# main_board.net
KiCad netlist of a schematic drawn in EAGLE
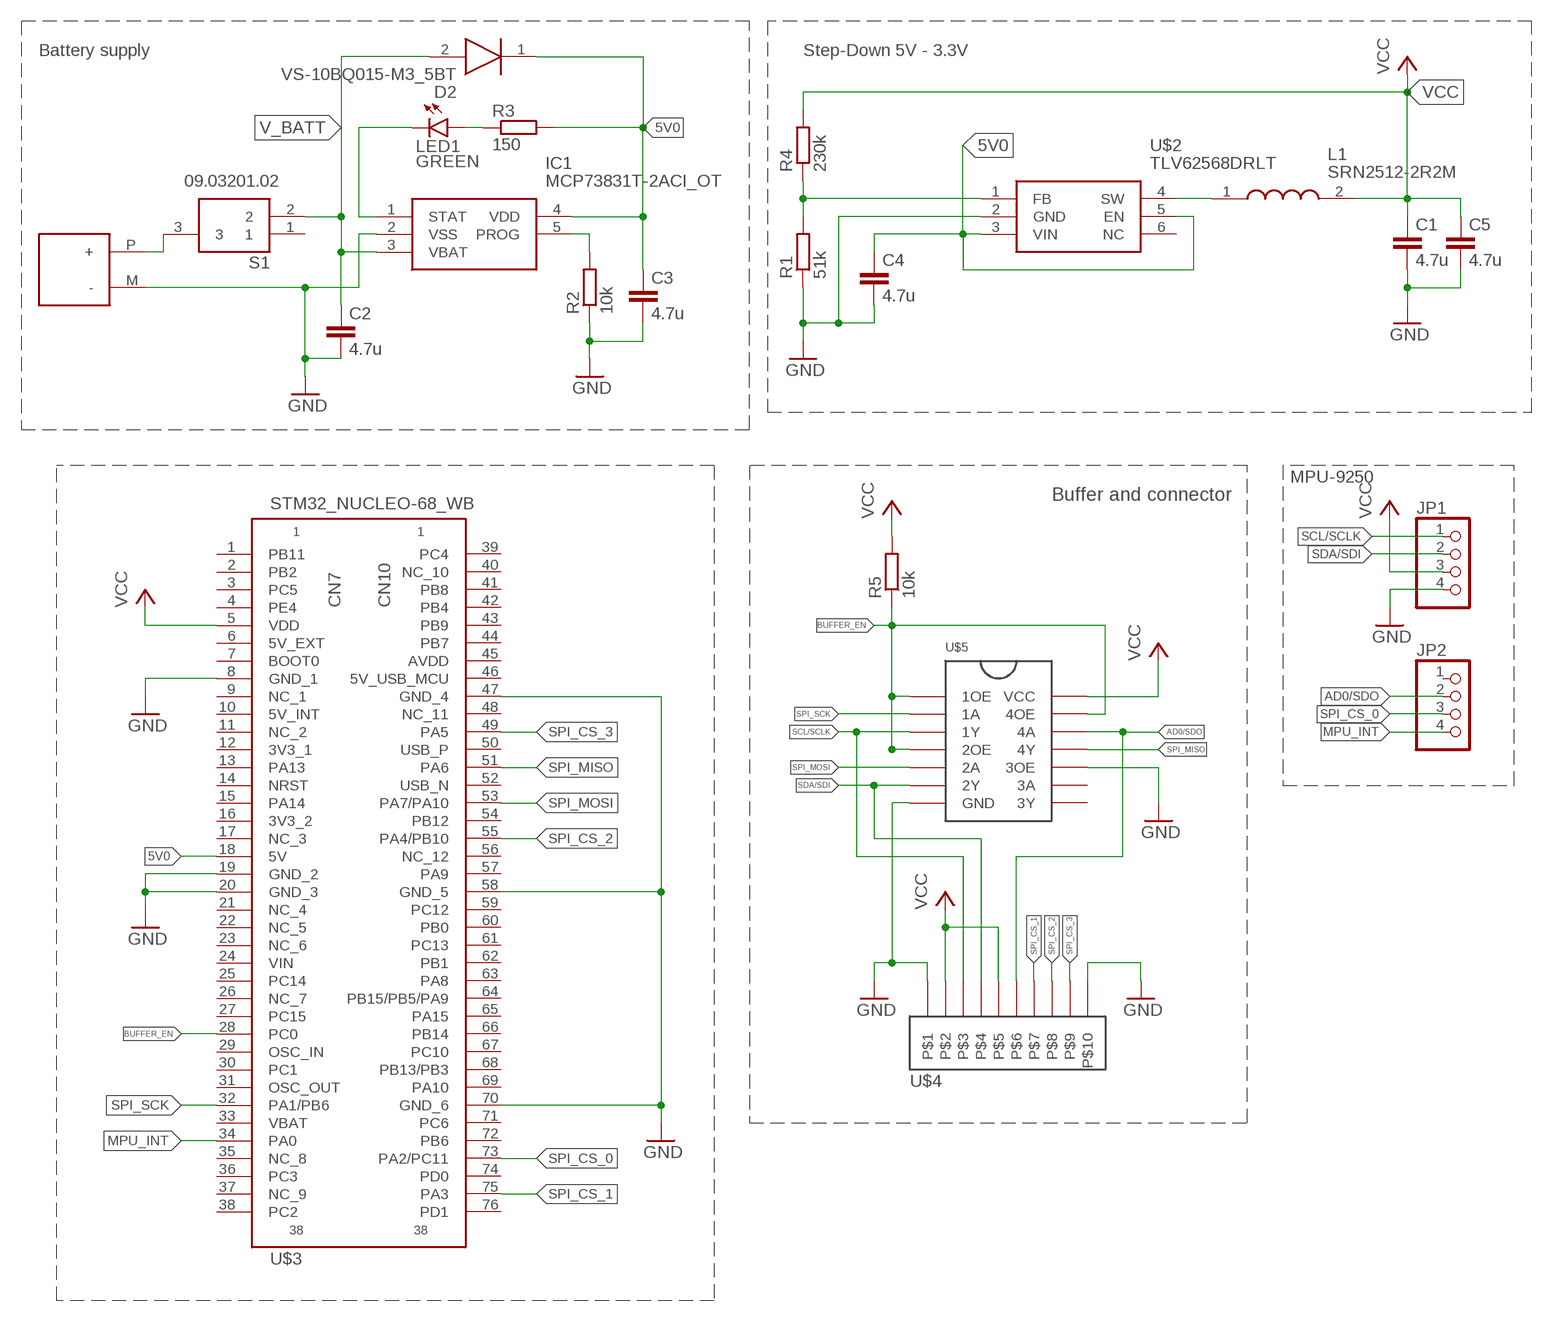
[diagram p0: schematic, sheet 1]

(export (version "E")
  (design (tool "Eeschema 10.0.6"))
  (components
    (comp (ref "C1")
      (value "4.7u")
      (footprint "eagle-import:C1206")
      (libsource (lib "eagle-import") (part "C-EUC1206"))
    )
    (comp (ref "C2")
      (value "4.7u")
      (footprint "eagle-import:C1206")
      (libsource (lib "eagle-import") (part "C-EUC1206"))
    )
    (comp (ref "C3")
      (value "4.7u")
      (footprint "eagle-import:C1206")
      (libsource (lib "eagle-import") (part "C-EUC1206"))
    )
    (comp (ref "C4")
      (value "4.7u")
      (footprint "eagle-import:C1206")
      (libsource (lib "eagle-import") (part "C-EUC1206"))
    )
    (comp (ref "C5")
      (value "4.7u")
      (footprint "eagle-import:C1206")
      (libsource (lib "eagle-import") (part "C-EUC1206"))
    )
    (comp (ref "D2")
      (value "VS-10BQ015-M3_5BT")
      (footprint "eagle-import:DIOM5436X244N")
      (fields
        (field (name "MANUFACTURER_PART_NUMBER") "VS-10BQ015-M3/5BT")
        (field (name "MOUSER_PART_NUMBER") "78-VS-10BQ015-M35BT")
      )
      (libsource (lib "eagle-import") (part "VS-10BQ015-M3_5BT"))
    )
    (comp (ref "IC1")
      (value "MCP73831T-2ACI_OT")
      (footprint "eagle-import:SOT95P270X145-5N")
      (fields
        (field (name "MANUFACTURER_PART_NUMBER") "MCP73831T-2ACI/OT")
        (field (name "MOUSER_PART_NUMBER") "579-MCP73831T-2ACIOT")
      )
      (libsource (lib "eagle-import") (part "MCP73831T-2ACI_OT"))
    )
    (comp (ref "JP1")
      (value "PINHD-1X04_2.54-SMD")
      (footprint "eagle-import:1X04SMD")
      (libsource (lib "eagle-import") (part "PINHD-1X04_2.54-SMD"))
    )
    (comp (ref "JP2")
      (value "PINHD-1X04_2.54-SMD")
      (footprint "eagle-import:1X04SMD")
      (libsource (lib "eagle-import") (part "PINHD-1X04_2.54-SMD"))
    )
    (comp (ref "L1")
      (value "SRN2512-2R2M")
      (footprint "eagle-import:INDPM2622X120N")
      (fields (field (name "MOUSER_PART_NUMBER") "652-SRN2512-2R2M"))
      (libsource (lib "eagle-import") (part "SRN2512-2R2M"))
    )
    (comp (ref "LED1")
      (value "GREEN")
      (footprint "eagle-import:CHIPLED_1206")
      (libsource (lib "eagle-import") (part "LEDCHIPLED_1206"))
    )
    (comp (ref "R1")
      (value "51k")
      (footprint "eagle-import:R1206")
      (libsource (lib "eagle-import") (part "R-EU_R1206"))
    )
    (comp (ref "R2")
      (value "10k")
      (footprint "eagle-import:R1206")
      (libsource (lib "eagle-import") (part "R-EU_R1206"))
    )
    (comp (ref "R3")
      (value "150")
      (footprint "eagle-import:R1206")
      (libsource (lib "eagle-import") (part "R-EU_R1206"))
    )
    (comp (ref "R4")
      (value "230k")
      (footprint "eagle-import:R1206")
      (libsource (lib "eagle-import") (part "R-EU_R1206"))
    )
    (comp (ref "R5")
      (value "10k")
      (footprint "eagle-import:R1206")
      (libsource (lib "eagle-import") (part "R-EU_R1206"))
    )
    (comp (ref "S1")
      (value "09.03201.02")
      (footprint "eagle-import:090320102")
      (fields (field (name "RS_PART_NUMBER") "1156283P"))
      (libsource (lib "eagle-import") (part "09.03201.02"))
    )
    (comp (ref "U$1")
      (value "BAT_FLAT_PAD")
      (footprint "eagle-import:BATTERY_FLAT_PAD")
      (libsource (lib "eagle-import") (part "BAT_FLAT_PAD"))
    )
    (comp (ref "U$2")
      (value "TLV62568DRLT")
      (footprint "eagle-import:SOT563")
      (libsource (lib "eagle-import") (part "TLV62568DRLT"))
    )
    (comp (ref "U$3")
      (value "STM32_NUCLEO-68_WB")
      (footprint "eagle-import:STM32_NUCLEO-68_FOOTPRINT")
      (libsource (lib "eagle-import") (part "STM32_NUCLEO-68_WB"))
    )
    (comp (ref "U$4")
      (value "1-2178711-2")
      (footprint "eagle-import:1-2178712-0")
      (libsource (lib "eagle-import") (part "1-2178711-2"))
    )
    (comp (ref "U$5")
      (value "74AHC126D,118")
      (footprint "eagle-import:SOIC127P600X175-14N")
      (libsource (lib "eagle-import") (part "74AHC126D,118"))
    )
  )
  (nets
    (net (code "1") (name "/3V3_1") (class "Default")
      (node (ref "U$3") (pin "12") (pinfunction "3V3_1_12") (pintype "power_in"))
    )
    (net (code "2") (name "/3V3_2") (class "Default")
      (node (ref "U$3") (pin "16") (pinfunction "3V3_2_16") (pintype "power_in"))
    )
    (net (code "3") (name "/5V_EXT") (class "Default")
      (node (ref "U$3") (pin "6") (pinfunction "5V_EXT_6") (pintype "power_in"))
    )
    (net (code "4") (name "/5V_INT") (class "Default")
      (node (ref "U$3") (pin "10") (pinfunction "5V_INT_10") (pintype "power_in"))
    )
    (net (code "5") (name "/5V_USB_MCU") (class "Default")
      (node (ref "U$3") (pin "46") (pinfunction "5V_USB_MCU_46") (pintype "power_in"))
    )
    (net (code "6") (name "/AVDD") (class "Default")
      (node (ref "U$3") (pin "45") (pinfunction "AVDD_45") (pintype "power_in"))
    )
    (net (code "7") (name "/VBAT") (class "Default")
      (node (ref "U$3") (pin "33") (pinfunction "VBAT_33") (pintype "power_in"))
    )
    (net (code "8") (name "/VIN") (class "Default")
      (node (ref "U$3") (pin "24") (pinfunction "VIN_24") (pintype "power_in"))
    )
    (net (code "9") (name "5V0") (class "Default")
      (node (ref "C3") (pin "1") (pinfunction "1_1") (pintype "passive"))
      (node (ref "C4") (pin "1") (pinfunction "1_1") (pintype "passive"))
      (node (ref "D2") (pin "1") (pinfunction "K_1") (pintype "bidirectional"))
      (node (ref "IC1") (pin "4") (pinfunction "VDD_4") (pintype "power_in"))
      (node (ref "R3") (pin "2") (pinfunction "2_2") (pintype "passive"))
      (node (ref "U$2") (pin "3") (pinfunction "VIN_3") (pintype "power_in"))
      (node (ref "U$2") (pin "5") (pinfunction "EN_5") (pintype "input"))
      (node (ref "U$3") (pin "18") (pinfunction "5V_18") (pintype "power_in"))
    )
    (net (code "10") (name "AD0{slash}SDO") (class "Default")
      (node (ref "JP2") (pin "2") (pinfunction "2_2") (pintype "passive"))
      (node (ref "U$4") (pin "P$6") (pinfunction "P$6_P$6") (pintype "bidirectional"))
      (node (ref "U$5") (pin "12") (pinfunction "4A_12") (pintype "bidirectional"))
    )
    (net (code "11") (name "BUFFER_EN") (class "Default")
      (node (ref "R5") (pin "1") (pinfunction "1_1") (pintype "passive"))
      (node (ref "U$3") (pin "28") (pinfunction "PC0_28") (pintype "bidirectional"))
      (node (ref "U$5") (pin "1") (pinfunction "1OE_1") (pintype "bidirectional"))
      (node (ref "U$5") (pin "13") (pinfunction "4OE_13") (pintype "bidirectional"))
      (node (ref "U$5") (pin "4") (pinfunction "2OE_4") (pintype "bidirectional"))
    )
    (net (code "12") (name "GND") (class "Default")
      (node (ref "C1") (pin "2") (pinfunction "2_2") (pintype "passive"))
      (node (ref "C2") (pin "2") (pinfunction "2_2") (pintype "passive"))
      (node (ref "C3") (pin "2") (pinfunction "2_2") (pintype "passive"))
      (node (ref "C4") (pin "2") (pinfunction "2_2") (pintype "passive"))
      (node (ref "C5") (pin "2") (pinfunction "2_2") (pintype "passive"))
      (node (ref "IC1") (pin "2") (pinfunction "VSS_2") (pintype "power_in"))
      (node (ref "JP1") (pin "4") (pinfunction "4_4") (pintype "passive"))
      (node (ref "R1") (pin "1") (pinfunction "1_1") (pintype "passive"))
      (node (ref "R2") (pin "1") (pinfunction "1_1") (pintype "passive"))
      (node (ref "U$1") (pin "M") (pinfunction "-_M") (pintype "bidirectional"))
      (node (ref "U$2") (pin "2") (pinfunction "GND_2") (pintype "power_in"))
      (node (ref "U$3") (pin "19") (pinfunction "GND_2_19") (pintype "power_in"))
      (node (ref "U$3") (pin "20") (pinfunction "GND_3_20") (pintype "power_in"))
      (node (ref "U$3") (pin "47") (pinfunction "GND_4_47") (pintype "power_in"))
      (node (ref "U$3") (pin "58") (pinfunction "GND_5_58") (pintype "power_in"))
      (node (ref "U$3") (pin "70") (pinfunction "GND_6_70") (pintype "power_in"))
      (node (ref "U$3") (pin "8") (pinfunction "GND_1_8") (pintype "power_in"))
      (node (ref "U$4") (pin "P$1") (pinfunction "P$1_P$1") (pintype "bidirectional"))
      (node (ref "U$4") (pin "P$10") (pinfunction "P$10_P$10") (pintype "bidirectional"))
      (node (ref "U$5") (pin "10") (pinfunction "3OE_10") (pintype "bidirectional"))
      (node (ref "U$5") (pin "7") (pinfunction "GND_7") (pintype "bidirectional"))
    )
    (net (code "13") (name "MPU_INT") (class "Default")
      (node (ref "JP2") (pin "4") (pinfunction "4_4") (pintype "passive"))
      (node (ref "U$3") (pin "34") (pinfunction "PA0_34") (pintype "bidirectional"))
    )
    (net (code "14") (name "Net-(IC1-PROG)") (class "Default")
      (node (ref "IC1") (pin "5") (pinfunction "PROG_5") (pintype "bidirectional"))
      (node (ref "R2") (pin "2") (pinfunction "2_2") (pintype "passive"))
    )
    (net (code "15") (name "Net-(IC1-STAT)") (class "Default")
      (node (ref "IC1") (pin "1") (pinfunction "STAT_1") (pintype "bidirectional"))
      (node (ref "LED1") (pin "C") (pinfunction "C_C") (pintype "passive"))
    )
    (net (code "16") (name "Net-(LED1-PadA)") (class "Default")
      (node (ref "LED1") (pin "A") (pinfunction "A_A") (pintype "passive"))
      (node (ref "R3") (pin "1") (pinfunction "1_1") (pintype "passive"))
    )
    (net (code "17") (name "Net-(U$1-+)") (class "Default")
      (node (ref "S1") (pin "3") (pinfunction "3_3") (pintype "bidirectional"))
      (node (ref "U$1") (pin "P") (pinfunction "+_P") (pintype "bidirectional"))
    )
    (net (code "18") (name "Net-(U$2-FB)") (class "Default")
      (node (ref "R1") (pin "2") (pinfunction "2_2") (pintype "passive"))
      (node (ref "R4") (pin "1") (pinfunction "1_1") (pintype "passive"))
      (node (ref "U$2") (pin "1") (pinfunction "FB_1") (pintype "input"))
    )
    (net (code "19") (name "Net-(U$2-SW)") (class "Default")
      (node (ref "L1") (pin "1") (pinfunction "1_1") (pintype "bidirectional"))
      (node (ref "U$2") (pin "4") (pinfunction "SW_4") (pintype "power_in"))
    )
    (net (code "20") (name "SCL{slash}SCLK") (class "Default")
      (node (ref "JP1") (pin "1") (pinfunction "1_1") (pintype "passive"))
      (node (ref "U$4") (pin "P$3") (pinfunction "P$3_P$3") (pintype "bidirectional"))
      (node (ref "U$5") (pin "3") (pinfunction "1Y_3") (pintype "bidirectional"))
    )
    (net (code "21") (name "SDA{slash}SDI") (class "Default")
      (node (ref "JP1") (pin "2") (pinfunction "2_2") (pintype "passive"))
      (node (ref "U$4") (pin "P$4") (pinfunction "P$4_P$4") (pintype "bidirectional"))
      (node (ref "U$5") (pin "6") (pinfunction "2Y_6") (pintype "bidirectional"))
    )
    (net (code "22") (name "SPI_CS_0") (class "Default")
      (node (ref "JP2") (pin "3") (pinfunction "3_3") (pintype "passive"))
      (node (ref "U$3") (pin "73") (pinfunction "PA2/PC11_73") (pintype "bidirectional"))
    )
    (net (code "23") (name "SPI_CS_1") (class "Default")
      (node (ref "U$3") (pin "75") (pinfunction "PA3_75") (pintype "bidirectional"))
      (node (ref "U$4") (pin "P$7") (pinfunction "P$7_P$7") (pintype "bidirectional"))
    )
    (net (code "24") (name "SPI_CS_2") (class "Default")
      (node (ref "U$3") (pin "55") (pinfunction "PA4/PB10_55") (pintype "bidirectional"))
      (node (ref "U$4") (pin "P$8") (pinfunction "P$8_P$8") (pintype "bidirectional"))
    )
    (net (code "25") (name "SPI_CS_3") (class "Default")
      (node (ref "U$3") (pin "49") (pinfunction "PA5_49") (pintype "bidirectional"))
      (node (ref "U$4") (pin "P$9") (pinfunction "P$9_P$9") (pintype "bidirectional"))
    )
    (net (code "26") (name "SPI_MISO") (class "Default")
      (node (ref "U$3") (pin "51") (pinfunction "PA6_51") (pintype "bidirectional"))
      (node (ref "U$5") (pin "11") (pinfunction "4Y_11") (pintype "bidirectional"))
    )
    (net (code "27") (name "SPI_MOSI") (class "Default")
      (node (ref "U$3") (pin "53") (pinfunction "PA7/PA10_53") (pintype "bidirectional"))
      (node (ref "U$5") (pin "5") (pinfunction "2A_5") (pintype "bidirectional"))
    )
    (net (code "28") (name "SPI_SCK") (class "Default")
      (node (ref "U$3") (pin "32") (pinfunction "PA1/PB6_32") (pintype "bidirectional"))
      (node (ref "U$5") (pin "2") (pinfunction "1A_2") (pintype "bidirectional"))
    )
    (net (code "29") (name "VCC") (class "Default")
      (node (ref "C1") (pin "1") (pinfunction "1_1") (pintype "passive"))
      (node (ref "C5") (pin "1") (pinfunction "1_1") (pintype "passive"))
      (node (ref "JP1") (pin "3") (pinfunction "3_3") (pintype "passive"))
      (node (ref "L1") (pin "2") (pinfunction "2_2") (pintype "bidirectional"))
      (node (ref "R4") (pin "2") (pinfunction "2_2") (pintype "passive"))
      (node (ref "R5") (pin "2") (pinfunction "2_2") (pintype "passive"))
      (node (ref "U$3") (pin "5") (pinfunction "VDD_5") (pintype "power_in"))
      (node (ref "U$4") (pin "P$2") (pinfunction "P$2_P$2") (pintype "bidirectional"))
      (node (ref "U$4") (pin "P$5") (pinfunction "P$5_P$5") (pintype "bidirectional"))
      (node (ref "U$5") (pin "14") (pinfunction "VCC_14") (pintype "bidirectional"))
    )
    (net (code "30") (name "V_BATT") (class "Default")
      (node (ref "C2") (pin "1") (pinfunction "1_1") (pintype "passive"))
      (node (ref "D2") (pin "2") (pinfunction "A_2") (pintype "bidirectional"))
      (node (ref "IC1") (pin "3") (pinfunction "VBAT_3") (pintype "bidirectional"))
      (node (ref "S1") (pin "2") (pinfunction "2_2") (pintype "bidirectional"))
    )
    (net (code "31") (name "unconnected-(JP2-Pad1)") (class "Default")
      (node (ref "JP2") (pin "1") (pinfunction "1_1") (pintype "passive"))
    )
    (net (code "32") (name "unconnected-(S1-Pad1)") (class "Default")
      (node (ref "S1") (pin "1") (pinfunction "1_1") (pintype "bidirectional"))
    )
    (net (code "33") (name "unconnected-(U$2-NC-Pad6)") (class "Default")
      (node (ref "U$2") (pin "6") (pinfunction "NC_6") (pintype "no_connect"))
    )
    (net (code "34") (name "unconnected-(U$3-BOOT0-Pad7)") (class "Default")
      (node (ref "U$3") (pin "7") (pinfunction "BOOT0_7") (pintype "bidirectional"))
    )
    (net (code "35") (name "unconnected-(U$3-NC_1-Pad9)") (class "Default")
      (node (ref "U$3") (pin "9") (pinfunction "NC_1_9") (pintype "no_connect"))
    )
    (net (code "36") (name "unconnected-(U$3-NC_2-Pad11)") (class "Default")
      (node (ref "U$3") (pin "11") (pinfunction "NC_2_11") (pintype "no_connect"))
    )
    (net (code "37") (name "unconnected-(U$3-NC_3-Pad17)") (class "Default")
      (node (ref "U$3") (pin "17") (pinfunction "NC_3_17") (pintype "no_connect"))
    )
    (net (code "38") (name "unconnected-(U$3-NC_4-Pad21)") (class "Default")
      (node (ref "U$3") (pin "21") (pinfunction "NC_4_21") (pintype "no_connect"))
    )
    (net (code "39") (name "unconnected-(U$3-NC_5-Pad22)") (class "Default")
      (node (ref "U$3") (pin "22") (pinfunction "NC_5_22") (pintype "no_connect"))
    )
    (net (code "40") (name "unconnected-(U$3-NC_6-Pad23)") (class "Default")
      (node (ref "U$3") (pin "23") (pinfunction "NC_6_23") (pintype "no_connect"))
    )
    (net (code "41") (name "unconnected-(U$3-NC_7-Pad26)") (class "Default")
      (node (ref "U$3") (pin "26") (pinfunction "NC_7_26") (pintype "no_connect"))
    )
    (net (code "42") (name "unconnected-(U$3-NC_8-Pad35)") (class "Default")
      (node (ref "U$3") (pin "35") (pinfunction "NC_8_35") (pintype "no_connect"))
    )
    (net (code "43") (name "unconnected-(U$3-NC_9-Pad37)") (class "Default")
      (node (ref "U$3") (pin "37") (pinfunction "NC_9_37") (pintype "no_connect"))
    )
    (net (code "44") (name "unconnected-(U$3-NC_10-Pad40)") (class "Default")
      (node (ref "U$3") (pin "40") (pinfunction "NC_10_40") (pintype "no_connect"))
    )
    (net (code "45") (name "unconnected-(U$3-NC_11-Pad48)") (class "Default")
      (node (ref "U$3") (pin "48") (pinfunction "NC_11_48") (pintype "no_connect"))
    )
    (net (code "46") (name "unconnected-(U$3-NC_12-Pad56)") (class "Default")
      (node (ref "U$3") (pin "56") (pinfunction "NC_12_56") (pintype "no_connect"))
    )
    (net (code "47") (name "unconnected-(U$3-NRST-Pad14)") (class "Default")
      (node (ref "U$3") (pin "14") (pinfunction "NRST_14") (pintype "bidirectional"))
    )
    (net (code "48") (name "unconnected-(U$3-OSC_IN-Pad29)") (class "Default")
      (node (ref "U$3") (pin "29") (pinfunction "OSC_IN_29") (pintype "bidirectional"))
    )
    (net (code "49") (name "unconnected-(U$3-OSC_OUT-Pad31)") (class "Default")
      (node (ref "U$3") (pin "31") (pinfunction "OSC_OUT_31") (pintype "bidirectional"))
    )
    (net (code "50") (name "unconnected-(U$3-PA8-Pad63)") (class "Default")
      (node (ref "U$3") (pin "63") (pinfunction "PA8_63") (pintype "bidirectional"))
    )
    (net (code "51") (name "unconnected-(U$3-PA9-Pad57)") (class "Default")
      (node (ref "U$3") (pin "57") (pinfunction "PA9_57") (pintype "bidirectional"))
    )
    (net (code "52") (name "unconnected-(U$3-PA10-Pad69)") (class "Default")
      (node (ref "U$3") (pin "69") (pinfunction "PA10_69") (pintype "bidirectional"))
    )
    (net (code "53") (name "unconnected-(U$3-PA13-Pad13)") (class "Default")
      (node (ref "U$3") (pin "13") (pinfunction "PA13_13") (pintype "bidirectional"))
    )
    (net (code "54") (name "unconnected-(U$3-PA14-Pad15)") (class "Default")
      (node (ref "U$3") (pin "15") (pinfunction "PA14_15") (pintype "bidirectional"))
    )
    (net (code "55") (name "unconnected-(U$3-PA15-Pad65)") (class "Default")
      (node (ref "U$3") (pin "65") (pinfunction "PA15_65") (pintype "bidirectional"))
    )
    (net (code "56") (name "unconnected-(U$3-PB0-Pad60)") (class "Default")
      (node (ref "U$3") (pin "60") (pinfunction "PB0_60") (pintype "bidirectional"))
    )
    (net (code "57") (name "unconnected-(U$3-PB1-Pad62)") (class "Default")
      (node (ref "U$3") (pin "62") (pinfunction "PB1_62") (pintype "bidirectional"))
    )
    (net (code "58") (name "unconnected-(U$3-PB2-Pad2)") (class "Default")
      (node (ref "U$3") (pin "2") (pinfunction "PB2_2") (pintype "bidirectional"))
    )
    (net (code "59") (name "unconnected-(U$3-PB4-Pad42)") (class "Default")
      (node (ref "U$3") (pin "42") (pinfunction "PB4_42") (pintype "bidirectional"))
    )
    (net (code "60") (name "unconnected-(U$3-PB6-Pad72)") (class "Default")
      (node (ref "U$3") (pin "72") (pinfunction "PB6_72") (pintype "bidirectional"))
    )
    (net (code "61") (name "unconnected-(U$3-PB7-Pad44)") (class "Default")
      (node (ref "U$3") (pin "44") (pinfunction "PB7_44") (pintype "bidirectional"))
    )
    (net (code "62") (name "unconnected-(U$3-PB8-Pad41)") (class "Default")
      (node (ref "U$3") (pin "41") (pinfunction "PB8_41") (pintype "bidirectional"))
    )
    (net (code "63") (name "unconnected-(U$3-PB9-Pad43)") (class "Default")
      (node (ref "U$3") (pin "43") (pinfunction "PB9_43") (pintype "bidirectional"))
    )
    (net (code "64") (name "unconnected-(U$3-PB11-Pad1)") (class "Default")
      (node (ref "U$3") (pin "1") (pinfunction "PB11_1") (pintype "bidirectional"))
    )
    (net (code "65") (name "unconnected-(U$3-PB12-Pad54)") (class "Default")
      (node (ref "U$3") (pin "54") (pinfunction "PB12_54") (pintype "bidirectional"))
    )
    (net (code "66") (name "unconnected-(U$3-PB13{slash}PB3-Pad68)") (class "Default")
      (node (ref "U$3") (pin "68") (pinfunction "PB13/PB3_68") (pintype "bidirectional"))
    )
    (net (code "67") (name "unconnected-(U$3-PB14-Pad66)") (class "Default")
      (node (ref "U$3") (pin "66") (pinfunction "PB14_66") (pintype "bidirectional"))
    )
    (net (code "68") (name "unconnected-(U$3-PB15{slash}PB5{slash}PA9-Pad64)") (class "Default")
      (node (ref "U$3") (pin "64") (pinfunction "PB15/PB5/PA9_64") (pintype "bidirectional"))
    )
    (net (code "69") (name "unconnected-(U$3-PC1-Pad30)") (class "Default")
      (node (ref "U$3") (pin "30") (pinfunction "PC1_30") (pintype "bidirectional"))
    )
    (net (code "70") (name "unconnected-(U$3-PC2-Pad38)") (class "Default")
      (node (ref "U$3") (pin "38") (pinfunction "PC2_38") (pintype "bidirectional"))
    )
    (net (code "71") (name "unconnected-(U$3-PC3-Pad36)") (class "Default")
      (node (ref "U$3") (pin "36") (pinfunction "PC3_36") (pintype "bidirectional"))
    )
    (net (code "72") (name "unconnected-(U$3-PC4-Pad39)") (class "Default")
      (node (ref "U$3") (pin "39") (pinfunction "PC4_39") (pintype "bidirectional"))
    )
    (net (code "73") (name "unconnected-(U$3-PC5-Pad3)") (class "Default")
      (node (ref "U$3") (pin "3") (pinfunction "PC5_3") (pintype "bidirectional"))
    )
    (net (code "74") (name "unconnected-(U$3-PC6-Pad71)") (class "Default")
      (node (ref "U$3") (pin "71") (pinfunction "PC6_71") (pintype "bidirectional"))
    )
    (net (code "75") (name "unconnected-(U$3-PC10-Pad67)") (class "Default")
      (node (ref "U$3") (pin "67") (pinfunction "PC10_67") (pintype "bidirectional"))
    )
    (net (code "76") (name "unconnected-(U$3-PC12-Pad59)") (class "Default")
      (node (ref "U$3") (pin "59") (pinfunction "PC12_59") (pintype "bidirectional"))
    )
    (net (code "77") (name "unconnected-(U$3-PC13-Pad61)") (class "Default")
      (node (ref "U$3") (pin "61") (pinfunction "PC13_61") (pintype "bidirectional"))
    )
    (net (code "78") (name "unconnected-(U$3-PC14-Pad25)") (class "Default")
      (node (ref "U$3") (pin "25") (pinfunction "PC14_25") (pintype "bidirectional"))
    )
    (net (code "79") (name "unconnected-(U$3-PC15-Pad27)") (class "Default")
      (node (ref "U$3") (pin "27") (pinfunction "PC15_27") (pintype "bidirectional"))
    )
    (net (code "80") (name "unconnected-(U$3-PD0-Pad74)") (class "Default")
      (node (ref "U$3") (pin "74") (pinfunction "PD0_74") (pintype "bidirectional"))
    )
    (net (code "81") (name "unconnected-(U$3-PD1-Pad76)") (class "Default")
      (node (ref "U$3") (pin "76") (pinfunction "PD1_76") (pintype "bidirectional"))
    )
    (net (code "82") (name "unconnected-(U$3-PE4-Pad4)") (class "Default")
      (node (ref "U$3") (pin "4") (pinfunction "PE4_4") (pintype "bidirectional"))
    )
    (net (code "83") (name "unconnected-(U$3-USB_N-Pad52)") (class "Default")
      (node (ref "U$3") (pin "52") (pinfunction "USB_N_52") (pintype "bidirectional"))
    )
    (net (code "84") (name "unconnected-(U$3-USB_P-Pad50)") (class "Default")
      (node (ref "U$3") (pin "50") (pinfunction "USB_P_50") (pintype "bidirectional"))
    )
    (net (code "85") (name "unconnected-(U$5-3A-Pad9)") (class "Default")
      (node (ref "U$5") (pin "9") (pinfunction "3A_9") (pintype "bidirectional"))
    )
    (net (code "86") (name "unconnected-(U$5-3Y-Pad8)") (class "Default")
      (node (ref "U$5") (pin "8") (pinfunction "3Y_8") (pintype "bidirectional"))
    )
  )
)
